# STorM32_NT_imu_v10_mini-mpu9250.net
KiCad netlist of a schematic drawn in EAGLE
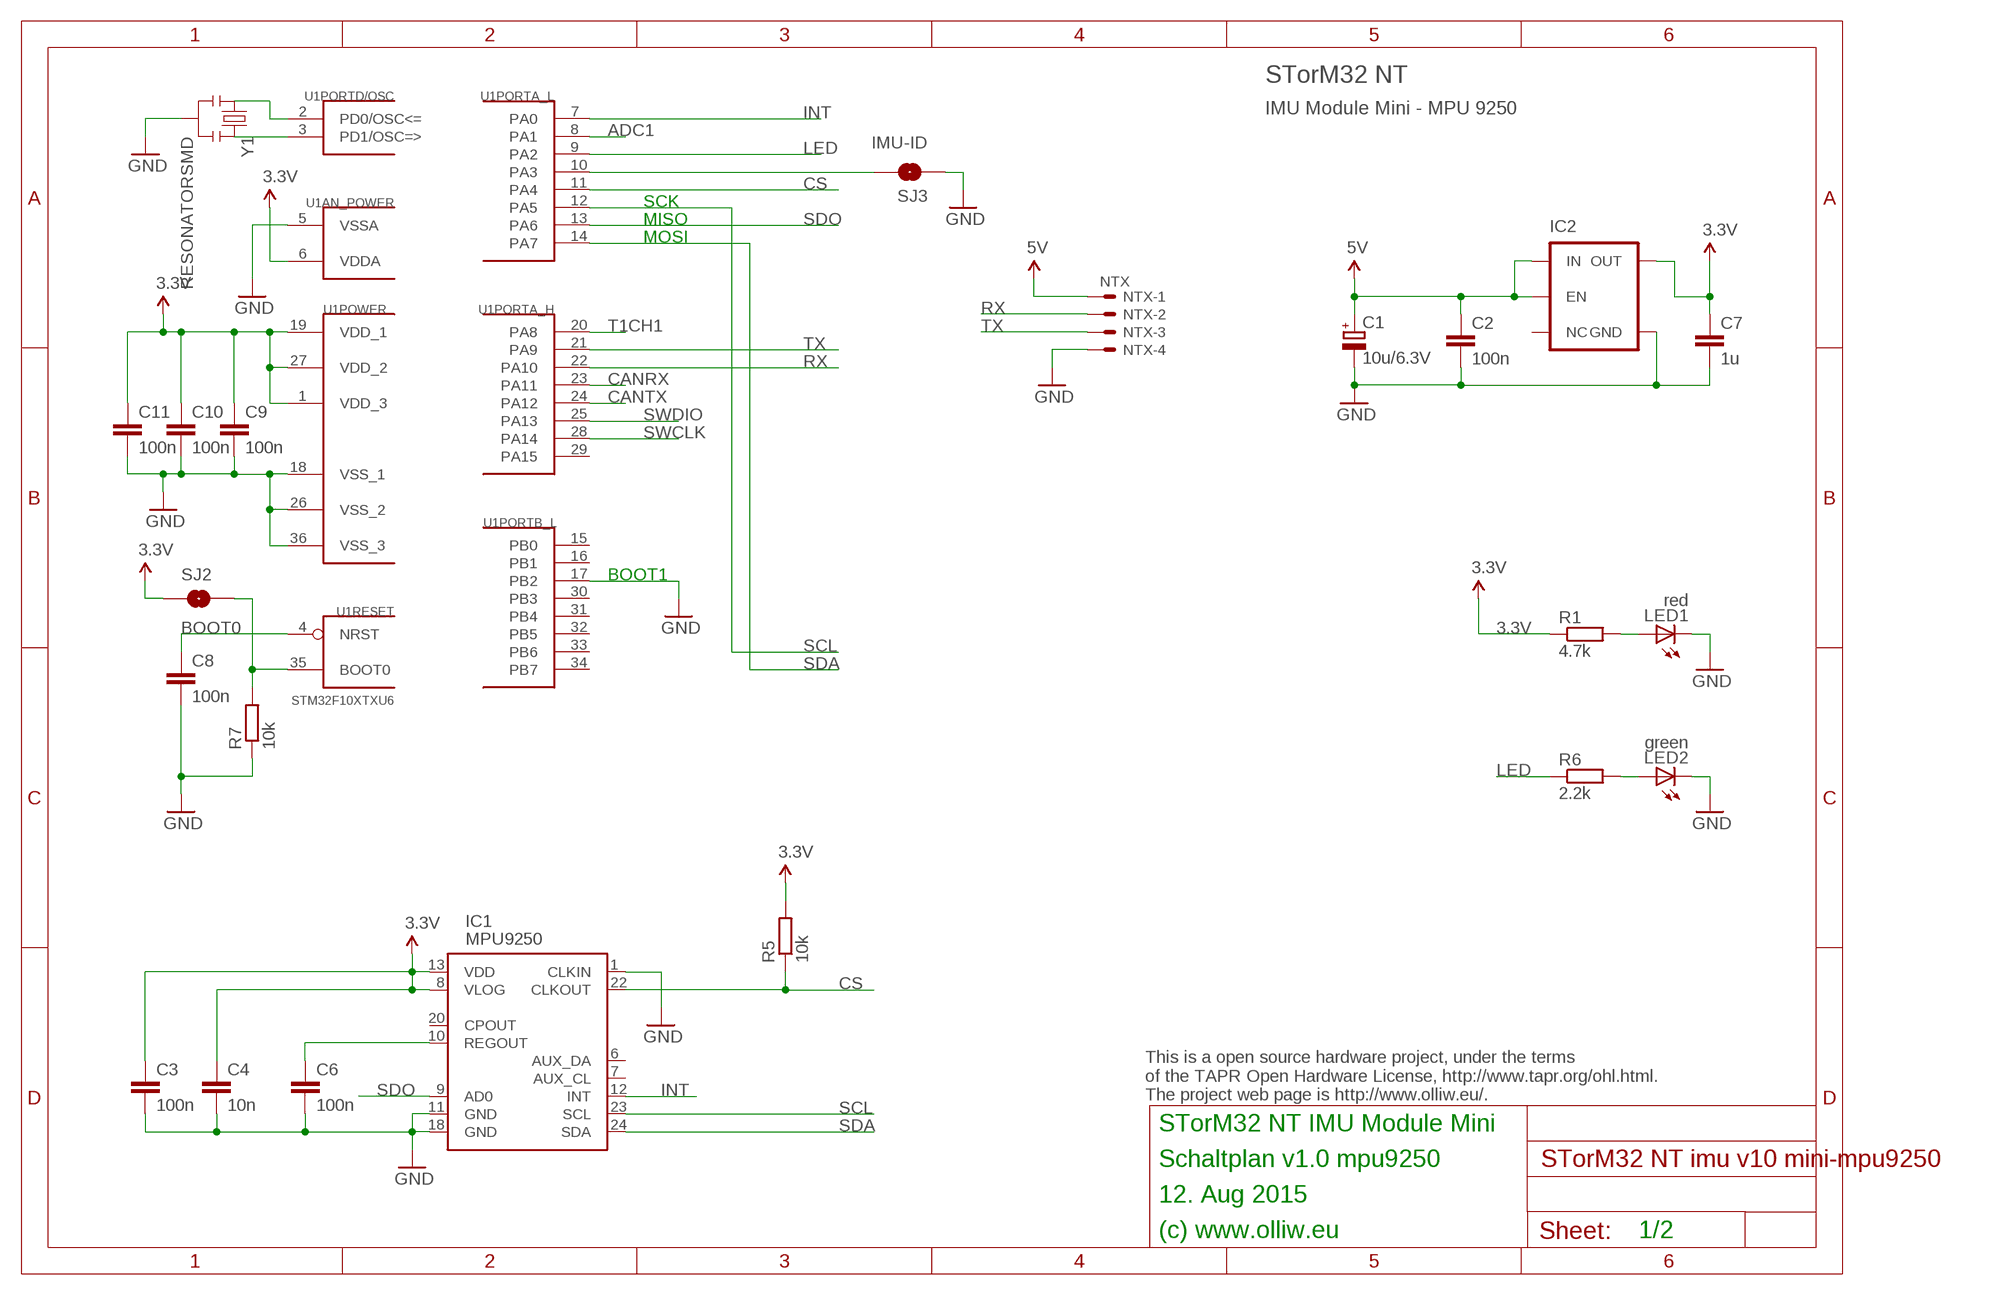
[diagram p0: schematic, sheet 1]

(export (version "E")
  (design (tool "Eeschema 10.0.6"))
  (components
    (comp (ref "C1")
      (value "10u/6.3V")
      (footprint "eagle-import:SMC_A")
      (libsource (lib "eagle-import") (part "CPOL-EUSMCA"))
    )
    (comp (ref "C2")
      (value "100n")
      (footprint "eagle-import:C0402")
      (libsource (lib "eagle-import") (part "C-EUC0402"))
    )
    (comp (ref "C3")
      (value "100n")
      (footprint "eagle-import:C0402")
      (libsource (lib "eagle-import") (part "C-EUC0402"))
    )
    (comp (ref "C4")
      (value "10n")
      (footprint "eagle-import:C0402")
      (libsource (lib "eagle-import") (part "C-EUC0402"))
    )
    (comp (ref "C6")
      (value "100n")
      (footprint "eagle-import:C0402")
      (libsource (lib "eagle-import") (part "C-EUC0402"))
    )
    (comp (ref "C7")
      (value "1u")
      (footprint "eagle-import:C0402")
      (libsource (lib "eagle-import") (part "C-EUC0402"))
    )
    (comp (ref "C8")
      (value "100n")
      (footprint "eagle-import:C0402")
      (libsource (lib "eagle-import") (part "C-EUC0402"))
    )
    (comp (ref "C9")
      (value "100n")
      (footprint "eagle-import:C0402")
      (libsource (lib "eagle-import") (part "C-EUC0402"))
    )
    (comp (ref "C10")
      (value "100n")
      (footprint "eagle-import:C0402")
      (libsource (lib "eagle-import") (part "C-EUC0402"))
    )
    (comp (ref "C11")
      (value "100n")
      (footprint "eagle-import:C0402")
      (libsource (lib "eagle-import") (part "C-EUC0402"))
    )
    (comp (ref "IC1")
      (value "MPU9250")
      (footprint "eagle-import:QFN-24-3X3")
      (libsource (lib "eagle-import") (part "IMU3000QFN-24-0.4MIL"))
    )
    (comp (ref "IC2")
      (value "V_REG_TPS76433SOT23-5")
      (footprint "eagle-import:SOT23-5")
      (libsource (lib "eagle-import") (part "V_REG_TPS76433SOT23-5"))
    )
    (comp (ref "LED1")
      (value "red")
      (footprint "eagle-import:CHIPLED_0603")
      (libsource (lib "eagle-import") (part "LEDCHIPLED_0603"))
    )
    (comp (ref "LED2")
      (value "green")
      (footprint "eagle-import:CHIPLED_0603")
      (libsource (lib "eagle-import") (part "LEDCHIPLED_0603"))
    )
    (comp (ref "NTX")
      (value "NTX")
      (footprint "eagle-import:SM04B-SRSS-TB")
      (libsource (lib "eagle-import") (part "?M04B-SRSS-TBS"))
    )
    (comp (ref "R1")
      (value "4.7k")
      (footprint "eagle-import:R0402")
      (libsource (lib "eagle-import") (part "R-EU_R0402"))
    )
    (comp (ref "R5")
      (value "10k")
      (footprint "eagle-import:R0402")
      (libsource (lib "eagle-import") (part "R-EU_R0402"))
    )
    (comp (ref "R6")
      (value "2.2k")
      (footprint "eagle-import:R0402")
      (libsource (lib "eagle-import") (part "R-EU_R0402"))
    )
    (comp (ref "R7")
      (value "10k")
      (footprint "eagle-import:R0402")
      (libsource (lib "eagle-import") (part "R-EU_R0402"))
    )
    (comp (ref "SJ2")
      (value "BOOT0")
      (footprint "eagle-import:SJ_2S-NO")
      (libsource (lib "eagle-import") (part "SOLDERJUMPERNO"))
    )
    (comp (ref "SJ3")
      (value "IMU-ID")
      (footprint "eagle-import:SJ_2S-NO")
      (libsource (lib "eagle-import") (part "SOLDERJUMPERNO"))
    )
    (comp (ref "U1")
      (value "STM32F10XTXU6")
      (footprint "eagle-import:VFQFPN36")
      (libsource (lib "eagle-import") (part "STM32F10XTXU6"))
    )
    (comp (ref "Y1")
      (value "RESONATORSMD")
      (footprint "eagle-import:RESONATOR-SMD")
      (libsource (lib "eagle-import") (part "RESONATORSMD"))
    )
  )
  (nets
    (net (code "1") (name "/ADC1") (class "Default")
      (node (ref "U1") (pin "8") (pinfunction "PA1_8") (pintype "bidirectional"))
    )
    (net (code "2") (name "/CANRX") (class "Default")
      (node (ref "U1") (pin "23") (pinfunction "PA11_23") (pintype "bidirectional"))
    )
    (net (code "3") (name "/CANTX") (class "Default")
      (node (ref "U1") (pin "24") (pinfunction "PA12_24") (pintype "bidirectional"))
    )
    (net (code "4") (name "/CS") (class "Default")
      (node (ref "IC1") (pin "22") (pinfunction "CLKOUT_22") (pintype "bidirectional"))
      (node (ref "R5") (pin "1") (pinfunction "1_1") (pintype "passive"))
      (node (ref "U1") (pin "11") (pinfunction "PA4_11") (pintype "bidirectional"))
    )
    (net (code "5") (name "/INT") (class "Default")
      (node (ref "IC1") (pin "12") (pinfunction "INT_12") (pintype "bidirectional"))
      (node (ref "U1") (pin "7") (pinfunction "PA0_7") (pintype "bidirectional"))
    )
    (net (code "6") (name "/LED") (class "Default")
      (node (ref "R6") (pin "1") (pinfunction "1_1") (pintype "passive"))
      (node (ref "U1") (pin "9") (pinfunction "PA2_9") (pintype "bidirectional"))
    )
    (net (code "7") (name "/RX") (class "Default")
      (node (ref "NTX") (pin "2") (pinfunction "S_2") (pintype "passive"))
      (node (ref "U1") (pin "22") (pinfunction "PA10_22") (pintype "bidirectional"))
    )
    (net (code "8") (name "/SCL") (class "Default")
      (node (ref "IC1") (pin "23") (pinfunction "SCL_23") (pintype "bidirectional"))
      (node (ref "U1") (pin "12") (pinfunction "PA5_12") (pintype "bidirectional"))
    )
    (net (code "9") (name "/SDA") (class "Default")
      (node (ref "IC1") (pin "24") (pinfunction "SDA_24") (pintype "bidirectional"))
      (node (ref "U1") (pin "14") (pinfunction "PA7_14") (pintype "bidirectional"))
    )
    (net (code "10") (name "/SDO") (class "Default")
      (node (ref "IC1") (pin "9") (pinfunction "AD0_9") (pintype "bidirectional"))
      (node (ref "U1") (pin "13") (pinfunction "PA6_13") (pintype "bidirectional"))
    )
    (net (code "11") (name "/SWCLK") (class "Default")
      (node (ref "U1") (pin "28") (pinfunction "PA14_28") (pintype "bidirectional"))
    )
    (net (code "12") (name "/SWDIO") (class "Default")
      (node (ref "U1") (pin "25") (pinfunction "PA13_25") (pintype "bidirectional"))
    )
    (net (code "13") (name "/T1CH1") (class "Default")
      (node (ref "U1") (pin "20") (pinfunction "PA8_20") (pintype "bidirectional"))
    )
    (net (code "14") (name "/TX") (class "Default")
      (node (ref "NTX") (pin "3") (pinfunction "S_3") (pintype "passive"))
      (node (ref "U1") (pin "21") (pinfunction "PA9_21") (pintype "bidirectional"))
    )
    (net (code "15") (name "3.3V") (class "Default")
      (node (ref "C10") (pin "1") (pinfunction "1_1") (pintype "passive"))
      (node (ref "C11") (pin "1") (pinfunction "1_1") (pintype "passive"))
      (node (ref "C3") (pin "1") (pinfunction "1_1") (pintype "passive"))
      (node (ref "C4") (pin "1") (pinfunction "1_1") (pintype "passive"))
      (node (ref "C7") (pin "1") (pinfunction "1_1") (pintype "passive"))
      (node (ref "C9") (pin "1") (pinfunction "1_1") (pintype "passive"))
      (node (ref "IC1") (pin "13") (pinfunction "VDD_13") (pintype "bidirectional"))
      (node (ref "IC1") (pin "8") (pinfunction "VLOG_8") (pintype "bidirectional"))
      (node (ref "IC2") (pin "5") (pinfunction "OUT_5") (pintype "passive"))
      (node (ref "R1") (pin "1") (pinfunction "1_1") (pintype "passive"))
      (node (ref "R5") (pin "2") (pinfunction "2_2") (pintype "passive"))
      (node (ref "SJ2") (pin "1") (pinfunction "1_1") (pintype "passive"))
      (node (ref "U1") (pin "1") (pinfunction "VDD_3_1") (pintype "power_in"))
      (node (ref "U1") (pin "19") (pinfunction "VDD_1_19") (pintype "power_in"))
      (node (ref "U1") (pin "27") (pinfunction "VDD_2_27") (pintype "power_in"))
      (node (ref "U1") (pin "6") (pinfunction "VDDA_6") (pintype "power_in"))
    )
    (net (code "16") (name "5V") (class "Default")
      (node (ref "C1") (pin "+") (pinfunction "+_+") (pintype "passive"))
      (node (ref "C2") (pin "1") (pinfunction "1_1") (pintype "passive"))
      (node (ref "IC2") (pin "1") (pinfunction "IN_1") (pintype "input"))
      (node (ref "IC2") (pin "3") (pinfunction "EN_3") (pintype "input"))
      (node (ref "NTX") (pin "1") (pinfunction "S_1") (pintype "passive"))
    )
    (net (code "17") (name "GND") (class "Default")
      (node (ref "C1") (pin "-") (pinfunction "-_-") (pintype "passive"))
      (node (ref "C10") (pin "2") (pinfunction "2_2") (pintype "passive"))
      (node (ref "C11") (pin "2") (pinfunction "2_2") (pintype "passive"))
      (node (ref "C2") (pin "2") (pinfunction "2_2") (pintype "passive"))
      (node (ref "C3") (pin "2") (pinfunction "2_2") (pintype "passive"))
      (node (ref "C4") (pin "2") (pinfunction "2_2") (pintype "passive"))
      (node (ref "C6") (pin "2") (pinfunction "2_2") (pintype "passive"))
      (node (ref "C7") (pin "2") (pinfunction "2_2") (pintype "passive"))
      (node (ref "C8") (pin "2") (pinfunction "2_2") (pintype "passive"))
      (node (ref "C9") (pin "2") (pinfunction "2_2") (pintype "passive"))
      (node (ref "IC1") (pin "1") (pinfunction "CLKIN_1") (pintype "bidirectional"))
      (node (ref "IC1") (pin "11") (pinfunction "GND_11") (pintype "bidirectional"))
      (node (ref "IC1") (pin "18") (pinfunction "GND_18") (pintype "bidirectional"))
      (node (ref "IC2") (pin "2") (pinfunction "GND_2") (pintype "input"))
      (node (ref "LED1") (pin "C") (pinfunction "C_C") (pintype "passive"))
      (node (ref "LED2") (pin "C") (pinfunction "C_C") (pintype "passive"))
      (node (ref "NTX") (pin "4") (pinfunction "S_4") (pintype "passive"))
      (node (ref "R7") (pin "1") (pinfunction "1_1") (pintype "passive"))
      (node (ref "SJ3") (pin "1") (pinfunction "1_1") (pintype "passive"))
      (node (ref "U1") (pin "17") (pinfunction "PB2_17") (pintype "bidirectional"))
      (node (ref "U1") (pin "18") (pinfunction "VSS_1_18") (pintype "power_in"))
      (node (ref "U1") (pin "26") (pinfunction "VSS_2_26") (pintype "power_in"))
      (node (ref "U1") (pin "36") (pinfunction "VSS_3_36") (pintype "power_in"))
      (node (ref "U1") (pin "5") (pinfunction "VSSA_5") (pintype "power_in"))
      (node (ref "Y1") (pin "2") (pinfunction "2_2") (pintype "passive"))
    )
    (net (code "18") (name "Net-(IC1-REGOUT)") (class "Default")
      (node (ref "C6") (pin "1") (pinfunction "1_1") (pintype "passive"))
      (node (ref "IC1") (pin "10") (pinfunction "REGOUT_10") (pintype "bidirectional"))
    )
    (net (code "19") (name "Net-(LED1-PadA)") (class "Default")
      (node (ref "LED1") (pin "A") (pinfunction "A_A") (pintype "passive"))
      (node (ref "R1") (pin "2") (pinfunction "2_2") (pintype "passive"))
    )
    (net (code "20") (name "Net-(LED2-PadA)") (class "Default")
      (node (ref "LED2") (pin "A") (pinfunction "A_A") (pintype "passive"))
      (node (ref "R6") (pin "2") (pinfunction "2_2") (pintype "passive"))
    )
    (net (code "21") (name "Net-(U1C-PA3)") (class "Default")
      (node (ref "SJ3") (pin "2") (pinfunction "2_2") (pintype "passive"))
      (node (ref "U1") (pin "10") (pinfunction "PA3_10") (pintype "bidirectional"))
    )
    (net (code "22") (name "Net-(U1E-PD0{slash}OSC<=)") (class "Default")
      (node (ref "U1") (pin "2") (pinfunction "PD0/OSC<=_2") (pintype "bidirectional"))
      (node (ref "Y1") (pin "1") (pinfunction "1_1") (pintype "passive"))
    )
    (net (code "23") (name "Net-(U1E-PD1{slash}OSC=>)") (class "Default")
      (node (ref "U1") (pin "3") (pinfunction "PD1/OSC=>_3") (pintype "bidirectional"))
      (node (ref "Y1") (pin "3") (pinfunction "3_3") (pintype "passive"))
    )
    (net (code "24") (name "Net-(U1G-BOOT0)") (class "Default")
      (node (ref "R7") (pin "2") (pinfunction "2_2") (pintype "passive"))
      (node (ref "SJ2") (pin "2") (pinfunction "2_2") (pintype "passive"))
      (node (ref "U1") (pin "35") (pinfunction "BOOT0_35") (pintype "input"))
    )
    (net (code "25") (name "Net-(U1G-NRST)") (class "Default")
      (node (ref "C8") (pin "1") (pinfunction "1_1") (pintype "passive"))
      (node (ref "U1") (pin "4") (pinfunction "NRST_4") (pintype "input"))
    )
    (net (code "26") (name "unconnected-(IC1-AUX_CL-Pad7)") (class "Default")
      (node (ref "IC1") (pin "7") (pinfunction "AUX_CL_7") (pintype "bidirectional"))
    )
    (net (code "27") (name "unconnected-(IC1-AUX_DA-Pad6)") (class "Default")
      (node (ref "IC1") (pin "6") (pinfunction "AUX_DA_6") (pintype "bidirectional"))
    )
    (net (code "28") (name "unconnected-(IC1-CPOUT-Pad20)") (class "Default")
      (node (ref "IC1") (pin "20") (pinfunction "CPOUT_20") (pintype "bidirectional"))
    )
    (net (code "29") (name "unconnected-(IC2-NC-Pad4)") (class "Default")
      (node (ref "IC2") (pin "4") (pinfunction "NC_4") (pintype "input"))
    )
    (net (code "30") (name "unconnected-(U1B-PA15-Pad29)") (class "Default")
      (node (ref "U1") (pin "29") (pinfunction "PA15_29") (pintype "bidirectional"))
    )
    (net (code "31") (name "unconnected-(U1D-PB0-Pad15)") (class "Default")
      (node (ref "U1") (pin "15") (pinfunction "PB0_15") (pintype "bidirectional"))
    )
    (net (code "32") (name "unconnected-(U1D-PB1-Pad16)") (class "Default")
      (node (ref "U1") (pin "16") (pinfunction "PB1_16") (pintype "bidirectional"))
    )
    (net (code "33") (name "unconnected-(U1D-PB3-Pad30)") (class "Default")
      (node (ref "U1") (pin "30") (pinfunction "PB3_30") (pintype "bidirectional"))
    )
    (net (code "34") (name "unconnected-(U1D-PB4-Pad31)") (class "Default")
      (node (ref "U1") (pin "31") (pinfunction "PB4_31") (pintype "bidirectional"))
    )
    (net (code "35") (name "unconnected-(U1D-PB5-Pad32)") (class "Default")
      (node (ref "U1") (pin "32") (pinfunction "PB5_32") (pintype "bidirectional"))
    )
    (net (code "36") (name "unconnected-(U1D-PB6-Pad33)") (class "Default")
      (node (ref "U1") (pin "33") (pinfunction "PB6_33") (pintype "bidirectional"))
    )
    (net (code "37") (name "unconnected-(U1D-PB7-Pad34)") (class "Default")
      (node (ref "U1") (pin "34") (pinfunction "PB7_34") (pintype "bidirectional"))
    )
  )
)
